# Attiny_pjon_v02.net
KiCad netlist of a schematic drawn in EAGLE
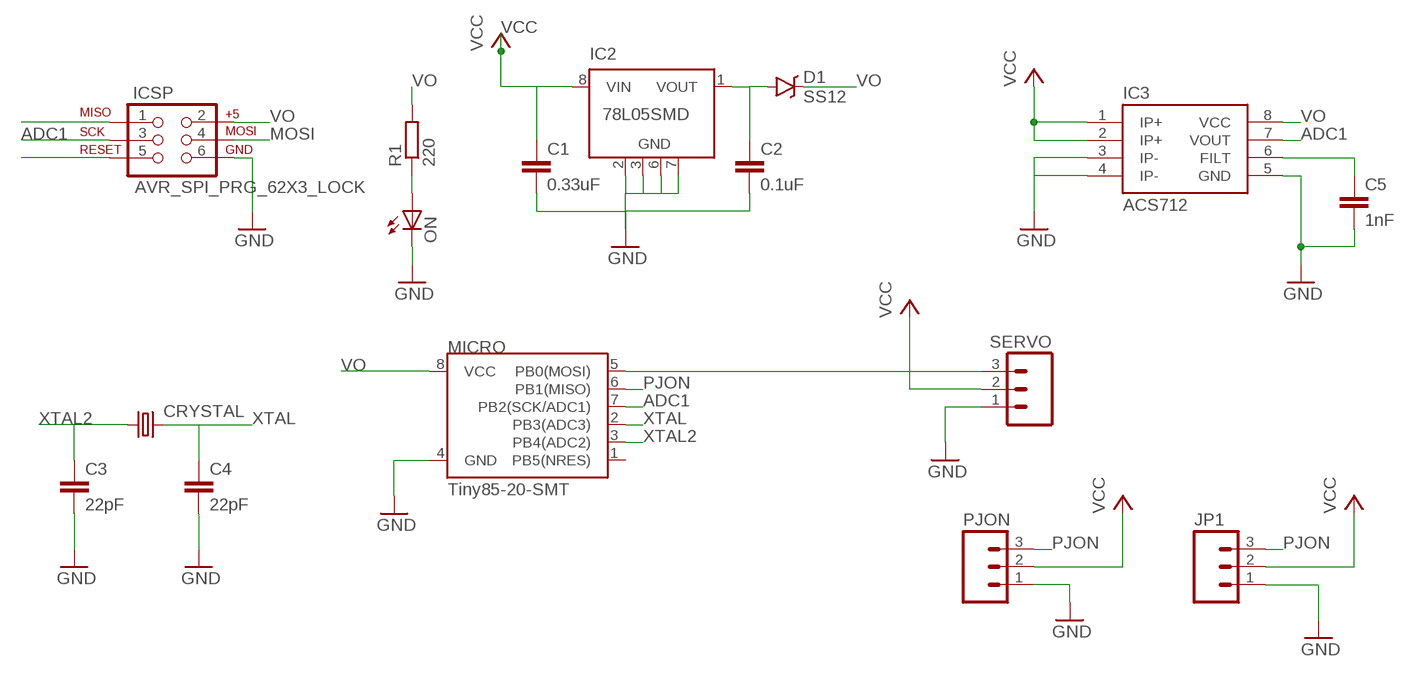
[diagram p0: schematic, sheet 1]

(export (version "E")
  (design (tool "Eeschema 10.0.6"))
  (components
    (comp (ref "C1")
      (value "0.33uF")
      (footprint "eagle-import:C1206")
      (libsource (lib "eagle-import") (part "C-EUC1206"))
    )
    (comp (ref "C2")
      (value "0.1uF")
      (footprint "eagle-import:C1206")
      (libsource (lib "eagle-import") (part "C-EUC1206"))
    )
    (comp (ref "C3")
      (value "22pF")
      (footprint "eagle-import:C1206")
      (libsource (lib "eagle-import") (part "C-EUC1206"))
    )
    (comp (ref "C4")
      (value "22pF")
      (footprint "eagle-import:C1206")
      (libsource (lib "eagle-import") (part "C-EUC1206"))
    )
    (comp (ref "C5")
      (value "1nF")
      (footprint "eagle-import:C1206")
      (libsource (lib "eagle-import") (part "C-EUC1206"))
    )
    (comp (ref "CRYSTAL")
      (value "CRYSTALSMD")
      (footprint "eagle-import:HC49UP")
      (libsource (lib "eagle-import") (part "CRYSTALSMD"))
    )
    (comp (ref "D1")
      (value "SS12")
      (footprint "eagle-import:SMA-DIODE")
      (libsource (lib "eagle-import") (part "DIODE-SCHOTTKY-B340A"))
    )
    (comp (ref "IC2")
      (value "78L05SMD")
      (footprint "eagle-import:SO08")
      (libsource (lib "eagle-import") (part "78LSMD05"))
    )
    (comp (ref "IC3")
      (value "ACS712")
      (footprint "eagle-import:SO08")
      (libsource (lib "eagle-import") (part "ACS712"))
    )
    (comp (ref "ICSP")
      (value "AVR_SPI_PRG_62X3_LOCK")
      (footprint "eagle-import:2X3_LOCK")
      (libsource (lib "eagle-import") (part "AVR_SPI_PRG_62X3_LOCK"))
    )
    (comp (ref "JP1")
      (value "M03PTH")
      (footprint "eagle-import:1X03")
      (libsource (lib "eagle-import") (part "M03PTH"))
    )
    (comp (ref "MICRO")
      (value "Tiny85-20-SMT")
      (footprint "eagle-import:SO08-EIAJ")
      (libsource (lib "eagle-import") (part "ATTINY45TINY85-20-SMT"))
    )
    (comp (ref "ON")
      (value "LEDSMT1206")
      (footprint "eagle-import:1206")
      (libsource (lib "eagle-import") (part "LEDSMT1206"))
    )
    (comp (ref "PJON")
      (value "M03PTH")
      (footprint "eagle-import:1X03")
      (libsource (lib "eagle-import") (part "M03PTH"))
    )
    (comp (ref "R1")
      (value "220")
      (footprint "eagle-import:R1206")
      (libsource (lib "eagle-import") (part "R-EU_R1206"))
    )
    (comp (ref "SERVO")
      (value "M03PTH")
      (footprint "eagle-import:1X03")
      (libsource (lib "eagle-import") (part "M03PTH"))
    )
  )
  (nets
    (net (code "1") (name "/ADC1") (class "Default")
      (node (ref "IC3") (pin "7") (pinfunction "VOUT_7") (pintype "bidirectional"))
      (node (ref "MICRO") (pin "7") (pinfunction "PB2(SCK/ADC1)_7") (pintype "bidirectional"))
    )
    (net (code "2") (name "/MOSI") (class "Default")
      (node (ref "ICSP") (pin "4") (pinfunction "4_4") (pintype "passive"))
      (node (ref "MICRO") (pin "5") (pinfunction "PB0(MOSI)_5") (pintype "bidirectional"))
      (node (ref "SERVO") (pin "3") (pinfunction "3_3") (pintype "passive"))
    )
    (net (code "3") (name "/PJON") (class "Default")
      (node (ref "ICSP") (pin "3") (pinfunction "3_3") (pintype "passive"))
      (node (ref "JP1") (pin "3") (pinfunction "3_3") (pintype "passive"))
      (node (ref "MICRO") (pin "6") (pinfunction "PB1(MISO)_6") (pintype "bidirectional"))
      (node (ref "PJON") (pin "3") (pinfunction "3_3") (pintype "passive"))
    )
    (net (code "4") (name "/VO") (class "Default")
      (node (ref "D1") (pin "C") (pinfunction "C_C") (pintype "passive"))
      (node (ref "IC3") (pin "8") (pinfunction "VCC_8") (pintype "bidirectional"))
      (node (ref "ICSP") (pin "2") (pinfunction "2_2") (pintype "passive"))
      (node (ref "MICRO") (pin "8") (pinfunction "VCC_8") (pintype "bidirectional"))
      (node (ref "R1") (pin "2") (pinfunction "2_2") (pintype "passive"))
    )
    (net (code "5") (name "/XTAL") (class "Default")
      (node (ref "C4") (pin "1") (pinfunction "1_1") (pintype "passive"))
      (node (ref "CRYSTAL") (pin "2") (pinfunction "2_2") (pintype "passive"))
      (node (ref "MICRO") (pin "2") (pinfunction "PB3(ADC3)_2") (pintype "bidirectional"))
    )
    (net (code "6") (name "/XTAL2") (class "Default")
      (node (ref "C3") (pin "1") (pinfunction "1_1") (pintype "passive"))
      (node (ref "CRYSTAL") (pin "1") (pinfunction "1_1") (pintype "passive"))
      (node (ref "MICRO") (pin "3") (pinfunction "PB4(ADC2)_3") (pintype "bidirectional"))
    )
    (net (code "7") (name "GND") (class "Default")
      (node (ref "C1") (pin "2") (pinfunction "2_2") (pintype "passive"))
      (node (ref "C2") (pin "2") (pinfunction "2_2") (pintype "passive"))
      (node (ref "C3") (pin "2") (pinfunction "2_2") (pintype "passive"))
      (node (ref "C4") (pin "2") (pinfunction "2_2") (pintype "passive"))
      (node (ref "C5") (pin "2") (pinfunction "2_2") (pintype "passive"))
      (node (ref "IC2") (pin "2") (pinfunction "GND_2") (pintype "power_in"))
      (node (ref "IC2") (pin "3") (pinfunction "GND_3") (pintype "power_in"))
      (node (ref "IC2") (pin "6") (pinfunction "GND_6") (pintype "power_in"))
      (node (ref "IC2") (pin "7") (pinfunction "GND_7") (pintype "power_in"))
      (node (ref "IC3") (pin "3") (pinfunction "IP-_3") (pintype "bidirectional"))
      (node (ref "IC3") (pin "4") (pinfunction "IP-_4") (pintype "bidirectional"))
      (node (ref "IC3") (pin "5") (pinfunction "GND_5") (pintype "bidirectional"))
      (node (ref "ICSP") (pin "6") (pinfunction "6_6") (pintype "passive"))
      (node (ref "JP1") (pin "1") (pinfunction "1_1") (pintype "passive"))
      (node (ref "MICRO") (pin "4") (pinfunction "GND_4") (pintype "bidirectional"))
      (node (ref "ON") (pin "C") (pinfunction "C_C") (pintype "passive"))
      (node (ref "PJON") (pin "1") (pinfunction "1_1") (pintype "passive"))
      (node (ref "SERVO") (pin "1") (pinfunction "1_1") (pintype "passive"))
    )
    (net (code "8") (name "Net-(IC2A-VOUT)") (class "Default")
      (node (ref "C2") (pin "1") (pinfunction "1_1") (pintype "passive"))
      (node (ref "D1") (pin "A") (pinfunction "A_A") (pintype "passive"))
      (node (ref "IC2") (pin "1") (pinfunction "VOUT_1") (pintype "output"))
    )
    (net (code "9") (name "Net-(IC3-FILT)") (class "Default")
      (node (ref "C5") (pin "1") (pinfunction "1_1") (pintype "passive"))
      (node (ref "IC3") (pin "6") (pinfunction "FILT_6") (pintype "bidirectional"))
    )
    (net (code "10") (name "Net-(ON-PadA)") (class "Default")
      (node (ref "ON") (pin "A") (pinfunction "A_A") (pintype "passive"))
      (node (ref "R1") (pin "1") (pinfunction "1_1") (pintype "passive"))
    )
    (net (code "11") (name "VCC") (class "Default")
      (node (ref "C1") (pin "1") (pinfunction "1_1") (pintype "passive"))
      (node (ref "IC2") (pin "8") (pinfunction "VIN_8") (pintype "passive"))
      (node (ref "IC3") (pin "1") (pinfunction "IP+_1") (pintype "bidirectional"))
      (node (ref "IC3") (pin "2") (pinfunction "IP+_2") (pintype "bidirectional"))
      (node (ref "JP1") (pin "2") (pinfunction "2_2") (pintype "passive"))
      (node (ref "PJON") (pin "2") (pinfunction "2_2") (pintype "passive"))
      (node (ref "SERVO") (pin "2") (pinfunction "2_2") (pintype "passive"))
    )
    (net (code "12") (name "unconnected-(ICSP-Pad1)") (class "Default")
      (node (ref "ICSP") (pin "1") (pinfunction "1_1") (pintype "passive"))
    )
    (net (code "13") (name "unconnected-(ICSP-Pad5)") (class "Default")
      (node (ref "ICSP") (pin "5") (pinfunction "5_5") (pintype "passive"))
    )
    (net (code "14") (name "unconnected-(MICRO-PB5(NRES)-Pad1)") (class "Default")
      (node (ref "MICRO") (pin "1") (pinfunction "PB5(NRES)_1") (pintype "bidirectional"))
    )
  )
)
